# Glasses-PSUBoard.net
KiCad netlist of a schematic drawn in Altium Designer
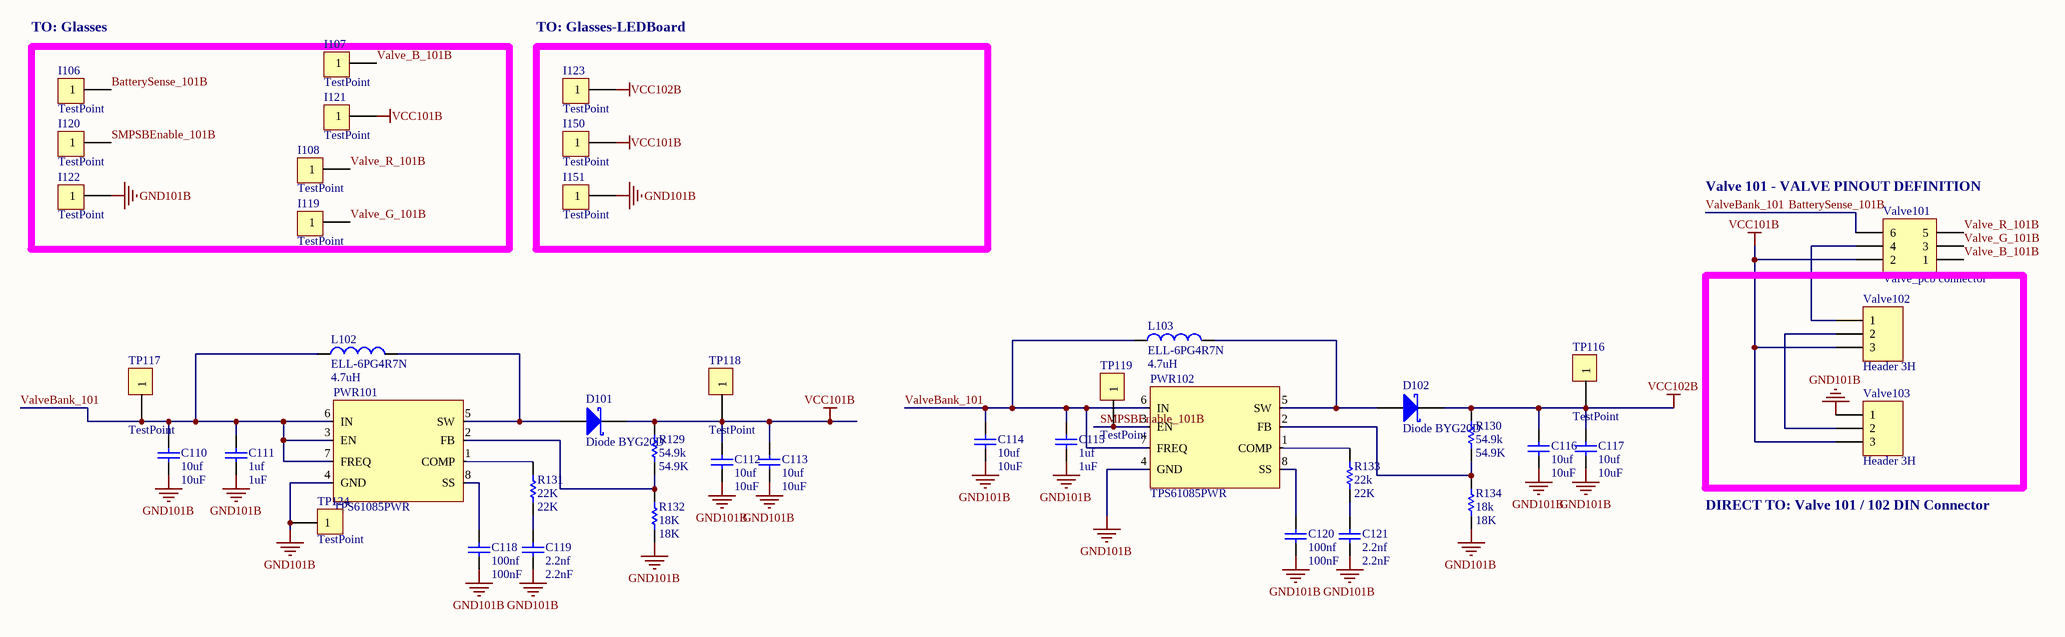
[diagram p0: Glasses-PSUBoard.SchDoc]

(export (version "E")
  (design (tool "Eeschema 10.0.6"))
  (components
    (comp (ref "C110")
      (value "10uf")
      (footprint "0805")
      (description "Capacitor (Semiconductor SIM Model)")
      (fields (field (name "ALTIUM_VALUE") "10uF") (field (name "PUBLISHER") "Altium Limited"))
      (libsource (lib "Miscellaneous Devices") (part "Cap Semi"))
    )
    (comp (ref "C111")
      (value "1uf")
      (footprint "0603")
      (description "Capacitor (Semiconductor SIM Model)")
      (fields (field (name "ALTIUM_VALUE") "1uF") (field (name "PUBLISHER") "Altium Limited"))
      (libsource (lib "Miscellaneous Devices") (part "Cap Semi"))
    )
    (comp (ref "C112")
      (value "10uf")
      (footprint "0805")
      (description "Capacitor (Semiconductor SIM Model)")
      (fields (field (name "ALTIUM_VALUE") "10uF") (field (name "PUBLISHER") "Altium Limited"))
      (libsource (lib "Miscellaneous Devices") (part "Cap Semi"))
    )
    (comp (ref "C113")
      (value "10uf")
      (footprint "0805")
      (description "Capacitor (Semiconductor SIM Model)")
      (fields (field (name "ALTIUM_VALUE") "10uF") (field (name "PUBLISHER") "Altium Limited"))
      (libsource (lib "Miscellaneous Devices") (part "Cap Semi"))
    )
    (comp (ref "C114")
      (value "10uf")
      (footprint "0805")
      (description "Capacitor (Semiconductor SIM Model)")
      (fields (field (name "ALTIUM_VALUE") "10uF") (field (name "PUBLISHER") "Altium Limited"))
      (libsource (lib "Miscellaneous Devices") (part "Cap Semi"))
    )
    (comp (ref "C115")
      (value "1uf")
      (footprint "0603")
      (description "Capacitor (Semiconductor SIM Model)")
      (fields (field (name "ALTIUM_VALUE") "1uF") (field (name "PUBLISHER") "Altium Limited"))
      (libsource (lib "Miscellaneous Devices") (part "Cap Semi"))
    )
    (comp (ref "C116")
      (value "10uf")
      (footprint "0805")
      (description "Capacitor (Semiconductor SIM Model)")
      (fields (field (name "ALTIUM_VALUE") "10uF") (field (name "PUBLISHER") "Altium Limited"))
      (libsource (lib "Miscellaneous Devices") (part "Cap Semi"))
    )
    (comp (ref "C117")
      (value "10uf")
      (footprint "0805")
      (description "Capacitor (Semiconductor SIM Model)")
      (fields (field (name "ALTIUM_VALUE") "10uF") (field (name "PUBLISHER") "Altium Limited"))
      (libsource (lib "Miscellaneous Devices") (part "Cap Semi"))
    )
    (comp (ref "C118")
      (value "100nf")
      (footprint "0603")
      (description "Capacitor (Semiconductor SIM Model)")
      (fields (field (name "ALTIUM_VALUE") "100nF") (field (name "PUBLISHER") "Altium Limited"))
      (libsource (lib "Miscellaneous Devices") (part "Cap Semi"))
    )
    (comp (ref "C119")
      (value "2.2nf")
      (footprint "0603")
      (description "Capacitor (Semiconductor SIM Model)")
      (fields (field (name "ALTIUM_VALUE") "2.2nF") (field (name "PUBLISHER") "Altium Limited"))
      (libsource (lib "Miscellaneous Devices") (part "Cap Semi"))
    )
    (comp (ref "C120")
      (value "100nf")
      (footprint "0603")
      (description "Capacitor (Semiconductor SIM Model)")
      (fields (field (name "ALTIUM_VALUE") "100nF") (field (name "PUBLISHER") "Altium Limited"))
      (libsource (lib "Miscellaneous Devices") (part "Cap Semi"))
    )
    (comp (ref "C121")
      (value "2.2nf")
      (footprint "0603")
      (description "Capacitor (Semiconductor SIM Model)")
      (fields (field (name "ALTIUM_VALUE") "2.2nF") (field (name "PUBLISHER") "Altium Limited"))
      (libsource (lib "Miscellaneous Devices") (part "Cap Semi"))
    )
    (comp (ref "D101")
      (value "Diode BYG20D")
      (footprint "BYG20J-E3")
      (description "Schottky Rectifier")
      (fields (field (name "PUBLISHER") "Altium Limited"))
      (libsource (lib "Miscellaneous Devices") (part "Diode 10TQ035"))
    )
    (comp (ref "D102")
      (value "Diode BYG20D")
      (footprint "BYG20J-E3")
      (description "Schottky Rectifier")
      (fields (field (name "PUBLISHER") "Altium Limited"))
      (libsource (lib "Miscellaneous Devices") (part "Diode 10TQ035"))
    )
    (comp (ref "I106")
      (value "TestPoint")
      (footprint "TestPoint")
      (libsource (lib "Schlib1") (part "TestPoint"))
    )
    (comp (ref "I107")
      (value "TestPoint")
      (footprint "TestPoint")
      (libsource (lib "Schlib1") (part "TestPoint"))
    )
    (comp (ref "I108")
      (value "TestPoint")
      (footprint "TestPoint")
      (libsource (lib "Schlib1") (part "TestPoint"))
    )
    (comp (ref "I119")
      (value "TestPoint")
      (footprint "TestPoint")
      (libsource (lib "Schlib1") (part "TestPoint"))
    )
    (comp (ref "I120")
      (value "TestPoint")
      (footprint "TestPoint")
      (libsource (lib "Schlib1") (part "TestPoint"))
    )
    (comp (ref "I121")
      (value "TestPoint")
      (footprint "TestPoint")
      (libsource (lib "Schlib1") (part "TestPoint"))
    )
    (comp (ref "I122")
      (value "TestPoint")
      (footprint "TestPoint")
      (libsource (lib "Schlib1") (part "TestPoint"))
    )
    (comp (ref "I123")
      (value "TestPoint")
      (footprint "TestPoint")
      (libsource (lib "Schlib1") (part "TestPoint"))
    )
    (comp (ref "I150")
      (value "TestPoint")
      (footprint "TestPoint")
      (libsource (lib "Schlib1") (part "TestPoint"))
    )
    (comp (ref "I151")
      (value "TestPoint")
      (footprint "TestPoint")
      (libsource (lib "Schlib1") (part "TestPoint"))
    )
    (comp (ref "L102")
      (value "ELL-6PG4R7N")
      (footprint "ELL6PG4R7N-2CHK")
      (description "Inductor")
      (fields (field (name "ALTIUM_VALUE") "4.7uH") (field (name "PUBLISHER") "Altium Limited"))
      (libsource (lib "Miscellaneous Devices") (part "Inductor"))
    )
    (comp (ref "L103")
      (value "ELL-6PG4R7N")
      (footprint "ELL6PG4R7N-2CHK")
      (description "Inductor")
      (fields (field (name "ALTIUM_VALUE") "4.7uH") (field (name "PUBLISHER") "Altium Limited"))
      (libsource (lib "Miscellaneous Devices") (part "Inductor"))
    )
    (comp (ref "PWR101")
      (value "TPS61085PWR")
      (footprint "TPS61085-MSOP8")
      (libsource (lib "Schlib1") (part "TPS61085PWR"))
    )
    (comp (ref "PWR102")
      (value "TPS61085PWR")
      (footprint "TPS61085-MSOP8")
      (libsource (lib "Schlib1") (part "TPS61085PWR"))
    )
    (comp (ref "R129")
      (value "54.9k")
      (footprint "0603")
      (description "Resistor")
      (fields (field (name "ALTIUM_VALUE") "54.9K") (field (name "PUBLISHER") "Altium Limited"))
      (libsource (lib "Miscellaneous Devices") (part "Res1"))
    )
    (comp (ref "R130")
      (value "54.9k")
      (footprint "0603")
      (description "Resistor")
      (fields (field (name "ALTIUM_VALUE") "54.9K") (field (name "PUBLISHER") "Altium Limited"))
      (libsource (lib "Miscellaneous Devices") (part "Res1"))
    )
    (comp (ref "R131")
      (value "22K")
      (footprint "0603")
      (description "Resistor")
      (fields (field (name "ALTIUM_VALUE") "22K") (field (name "PUBLISHER") "Altium Limited"))
      (libsource (lib "Miscellaneous Devices") (part "Res1"))
    )
    (comp (ref "R132")
      (value "18K")
      (footprint "0603")
      (description "Resistor")
      (fields (field (name "ALTIUM_VALUE") "18K") (field (name "PUBLISHER") "Altium Limited"))
      (libsource (lib "Miscellaneous Devices") (part "Res1"))
    )
    (comp (ref "R133")
      (value "22k")
      (footprint "0603")
      (description "Resistor")
      (fields (field (name "ALTIUM_VALUE") "22K") (field (name "PUBLISHER") "Altium Limited"))
      (libsource (lib "Miscellaneous Devices") (part "Res1"))
    )
    (comp (ref "R134")
      (value "18k")
      (footprint "0603")
      (description "Resistor")
      (fields (field (name "ALTIUM_VALUE") "18K") (field (name "PUBLISHER") "Altium Limited"))
      (libsource (lib "Miscellaneous Devices") (part "Res1"))
    )
    (comp (ref "TP116") (value "TestPoint") (footprint "TestPoint") (libsource (lib "") (part "TestPoint_1")))
    (comp (ref "TP117") (value "TestPoint") (footprint "TestPoint") (libsource (lib "") (part "TestPoint_1")))
    (comp (ref "TP118") (value "TestPoint") (footprint "TestPoint") (libsource (lib "") (part "TestPoint_1")))
    (comp (ref "TP119") (value "TestPoint") (footprint "TestPoint") (libsource (lib "") (part "TestPoint_1")))
    (comp (ref "TP124") (value "TestPoint") (footprint "TestPoint") (libsource (lib "") (part "TestPoint_2")))
    (comp (ref "Valve101")
      (value "Valve_pcb connector")
      (footprint "Valve_pcb mount")
      (description "Header, 3-Pin, Dual row, Right Angle")
      (fields (field (name "PUBLISHER") "Altium Limited"))
      (libsource (lib "Miscellaneous Connectors") (part "Header 3X2H"))
    )
    (comp (ref "Valve102")
      (value "Header 3H")
      (footprint "Valve_3 pin")
      (description "Header, 3-Pin, Right Angle")
      (fields (field (name "PUBLISHER") "Altium Limited"))
      (libsource (lib "Miscellaneous Connectors") (part "Header 3H"))
    )
    (comp (ref "Valve103")
      (value "Header 3H")
      (footprint "Valve_3 pin")
      (description "Header, 3-Pin, Right Angle")
      (fields (field (name "PUBLISHER") "Altium Limited"))
      (libsource (lib "Miscellaneous Connectors") (part "Header 3H"))
    )
  )
  (nets
    (net (code "1") (name "/BatterySense_101B") (class "Default")
      (node (ref "C110") (pin "2") (pinfunction "2_2") (pintype "passive"))
      (node (ref "C111") (pin "2") (pinfunction "2_2") (pintype "passive"))
      (node (ref "C114") (pin "2") (pinfunction "2_2") (pintype "passive"))
      (node (ref "C115") (pin "2") (pinfunction "2_2") (pintype "passive"))
      (node (ref "I106") (pin "1") (pinfunction "1_1") (pintype "passive"))
      (node (ref "L102") (pin "1") (pinfunction "1_1") (pintype "passive"))
      (node (ref "L103") (pin "1") (pinfunction "1_1") (pintype "passive"))
      (node (ref "PWR101") (pin "3") (pinfunction "EN_3") (pintype "passive"))
      (node (ref "PWR101") (pin "6") (pinfunction "IN_6") (pintype "passive"))
      (node (ref "PWR101") (pin "7") (pinfunction "FREQ_7") (pintype "passive"))
      (node (ref "PWR102") (pin "6") (pinfunction "IN_6") (pintype "passive"))
      (node (ref "PWR102") (pin "7") (pinfunction "FREQ_7") (pintype "passive"))
      (node (ref "TP117") (pin "1") (pinfunction "1_1") (pintype "passive"))
      (node (ref "Valve101") (pin "6") (pinfunction "6_6") (pintype "passive"))
    )
    (net (code "2") (name "/SMPSBEnable_101B") (class "Default")
      (node (ref "I120") (pin "1") (pinfunction "1_1") (pintype "passive"))
      (node (ref "PWR102") (pin "3") (pinfunction "EN_3") (pintype "passive"))
      (node (ref "TP119") (pin "1") (pinfunction "1_1") (pintype "passive"))
    )
    (net (code "3") (name "/Valve_B_101B") (class "Default")
      (node (ref "I107") (pin "1") (pinfunction "1_1") (pintype "passive"))
      (node (ref "Valve101") (pin "1") (pinfunction "1_1") (pintype "passive"))
    )
    (net (code "4") (name "/Valve_G_101B") (class "Default")
      (node (ref "I119") (pin "1") (pinfunction "1_1") (pintype "passive"))
      (node (ref "Valve101") (pin "3") (pinfunction "3_3") (pintype "passive"))
    )
    (net (code "5") (name "/Valve_R_101B") (class "Default")
      (node (ref "I108") (pin "1") (pinfunction "1_1") (pintype "passive"))
      (node (ref "Valve101") (pin "5") (pinfunction "5_5") (pintype "passive"))
    )
    (net (code "6") (name "GND101B") (class "Default")
      (node (ref "C110") (pin "1") (pinfunction "1_1") (pintype "passive"))
      (node (ref "C111") (pin "1") (pinfunction "1_1") (pintype "passive"))
      (node (ref "C112") (pin "1") (pinfunction "1_1") (pintype "passive"))
      (node (ref "C113") (pin "1") (pinfunction "1_1") (pintype "passive"))
      (node (ref "C114") (pin "1") (pinfunction "1_1") (pintype "passive"))
      (node (ref "C115") (pin "1") (pinfunction "1_1") (pintype "passive"))
      (node (ref "C116") (pin "1") (pinfunction "1_1") (pintype "passive"))
      (node (ref "C117") (pin "1") (pinfunction "1_1") (pintype "passive"))
      (node (ref "C118") (pin "1") (pinfunction "1_1") (pintype "passive"))
      (node (ref "C119") (pin "1") (pinfunction "1_1") (pintype "passive"))
      (node (ref "C120") (pin "1") (pinfunction "1_1") (pintype "passive"))
      (node (ref "C121") (pin "1") (pinfunction "1_1") (pintype "passive"))
      (node (ref "I122") (pin "1") (pinfunction "1_1") (pintype "passive"))
      (node (ref "I151") (pin "1") (pinfunction "1_1") (pintype "passive"))
      (node (ref "PWR101") (pin "4") (pinfunction "GND_4") (pintype "passive"))
      (node (ref "PWR102") (pin "4") (pinfunction "GND_4") (pintype "passive"))
      (node (ref "R132") (pin "1") (pinfunction "1_1") (pintype "passive"))
      (node (ref "R134") (pin "1") (pinfunction "1_1") (pintype "passive"))
      (node (ref "TP124") (pin "1") (pinfunction "1_1") (pintype "passive"))
      (node (ref "Valve103") (pin "1") (pinfunction "1_1") (pintype "passive"))
    )
    (net (code "7") (name "Net-(C119-Pad2)") (class "Default")
      (node (ref "C119") (pin "2") (pinfunction "2_2") (pintype "passive"))
      (node (ref "R131") (pin "1") (pinfunction "1_1") (pintype "passive"))
    )
    (net (code "8") (name "Net-(C121-Pad2)") (class "Default")
      (node (ref "C121") (pin "2") (pinfunction "2_2") (pintype "passive"))
      (node (ref "R133") (pin "1") (pinfunction "1_1") (pintype "passive"))
    )
    (net (code "9") (name "Net-(D101-A)") (class "Default")
      (node (ref "D101") (pin "3") (pinfunction "A_3") (pintype "passive"))
      (node (ref "L102") (pin "2") (pinfunction "2_2") (pintype "passive"))
      (node (ref "PWR101") (pin "5") (pinfunction "SW_5") (pintype "passive"))
    )
    (net (code "10") (name "Net-(D102-A)") (class "Default")
      (node (ref "D102") (pin "3") (pinfunction "A_3") (pintype "passive"))
      (node (ref "L103") (pin "2") (pinfunction "2_2") (pintype "passive"))
      (node (ref "PWR102") (pin "5") (pinfunction "SW_5") (pintype "passive"))
    )
    (net (code "11") (name "Net-(PWR101-COMP)") (class "Default")
      (node (ref "PWR101") (pin "1") (pinfunction "COMP_1") (pintype "passive"))
      (node (ref "R131") (pin "2") (pinfunction "2_2") (pintype "passive"))
    )
    (net (code "12") (name "Net-(PWR101-FB)") (class "Default")
      (node (ref "PWR101") (pin "2") (pinfunction "FB_2") (pintype "passive"))
      (node (ref "R129") (pin "1") (pinfunction "1_1") (pintype "passive"))
      (node (ref "R132") (pin "2") (pinfunction "2_2") (pintype "passive"))
    )
    (net (code "13") (name "Net-(PWR101-SS)") (class "Default")
      (node (ref "C118") (pin "2") (pinfunction "2_2") (pintype "passive"))
      (node (ref "PWR101") (pin "8") (pinfunction "SS_8") (pintype "passive"))
    )
    (net (code "14") (name "Net-(PWR102-COMP)") (class "Default")
      (node (ref "PWR102") (pin "1") (pinfunction "COMP_1") (pintype "passive"))
      (node (ref "R133") (pin "2") (pinfunction "2_2") (pintype "passive"))
    )
    (net (code "15") (name "Net-(PWR102-FB)") (class "Default")
      (node (ref "PWR102") (pin "2") (pinfunction "FB_2") (pintype "passive"))
      (node (ref "R130") (pin "1") (pinfunction "1_1") (pintype "passive"))
      (node (ref "R134") (pin "2") (pinfunction "2_2") (pintype "passive"))
    )
    (net (code "16") (name "Net-(PWR102-SS)") (class "Default")
      (node (ref "C120") (pin "2") (pinfunction "2_2") (pintype "passive"))
      (node (ref "PWR102") (pin "8") (pinfunction "SS_8") (pintype "passive"))
    )
    (net (code "17") (name "Net-(Valve101-Pad4)") (class "Default")
      (node (ref "Valve101") (pin "4") (pinfunction "4_4") (pintype "passive"))
      (node (ref "Valve102") (pin "1") (pinfunction "1_1") (pintype "passive"))
    )
    (net (code "18") (name "Net-(Valve102-Pad2)") (class "Default")
      (node (ref "Valve102") (pin "2") (pinfunction "2_2") (pintype "passive"))
      (node (ref "Valve103") (pin "2") (pinfunction "2_2") (pintype "passive"))
    )
    (net (code "19") (name "VCC101B") (class "Default")
      (node (ref "C112") (pin "2") (pinfunction "2_2") (pintype "passive"))
      (node (ref "C113") (pin "2") (pinfunction "2_2") (pintype "passive"))
      (node (ref "D101") (pin "1") (pinfunction "K_1") (pintype "passive"))
      (node (ref "I121") (pin "1") (pinfunction "1_1") (pintype "passive"))
      (node (ref "I150") (pin "1") (pinfunction "1_1") (pintype "passive"))
      (node (ref "R129") (pin "2") (pinfunction "2_2") (pintype "passive"))
      (node (ref "TP118") (pin "1") (pinfunction "1_1") (pintype "passive"))
      (node (ref "Valve101") (pin "2") (pinfunction "2_2") (pintype "passive"))
      (node (ref "Valve102") (pin "3") (pinfunction "3_3") (pintype "passive"))
      (node (ref "Valve103") (pin "3") (pinfunction "3_3") (pintype "passive"))
    )
    (net (code "20") (name "VCC102B") (class "Default")
      (node (ref "C116") (pin "2") (pinfunction "2_2") (pintype "passive"))
      (node (ref "C117") (pin "2") (pinfunction "2_2") (pintype "passive"))
      (node (ref "D102") (pin "1") (pinfunction "K_1") (pintype "passive"))
      (node (ref "I123") (pin "1") (pinfunction "1_1") (pintype "passive"))
      (node (ref "R130") (pin "2") (pinfunction "2_2") (pintype "passive"))
      (node (ref "TP116") (pin "1") (pinfunction "1_1") (pintype "passive"))
    )
  )
)
